# arduino_Uno_Rev3-02-TH.net
KiCad netlist of a schematic drawn in EAGLE
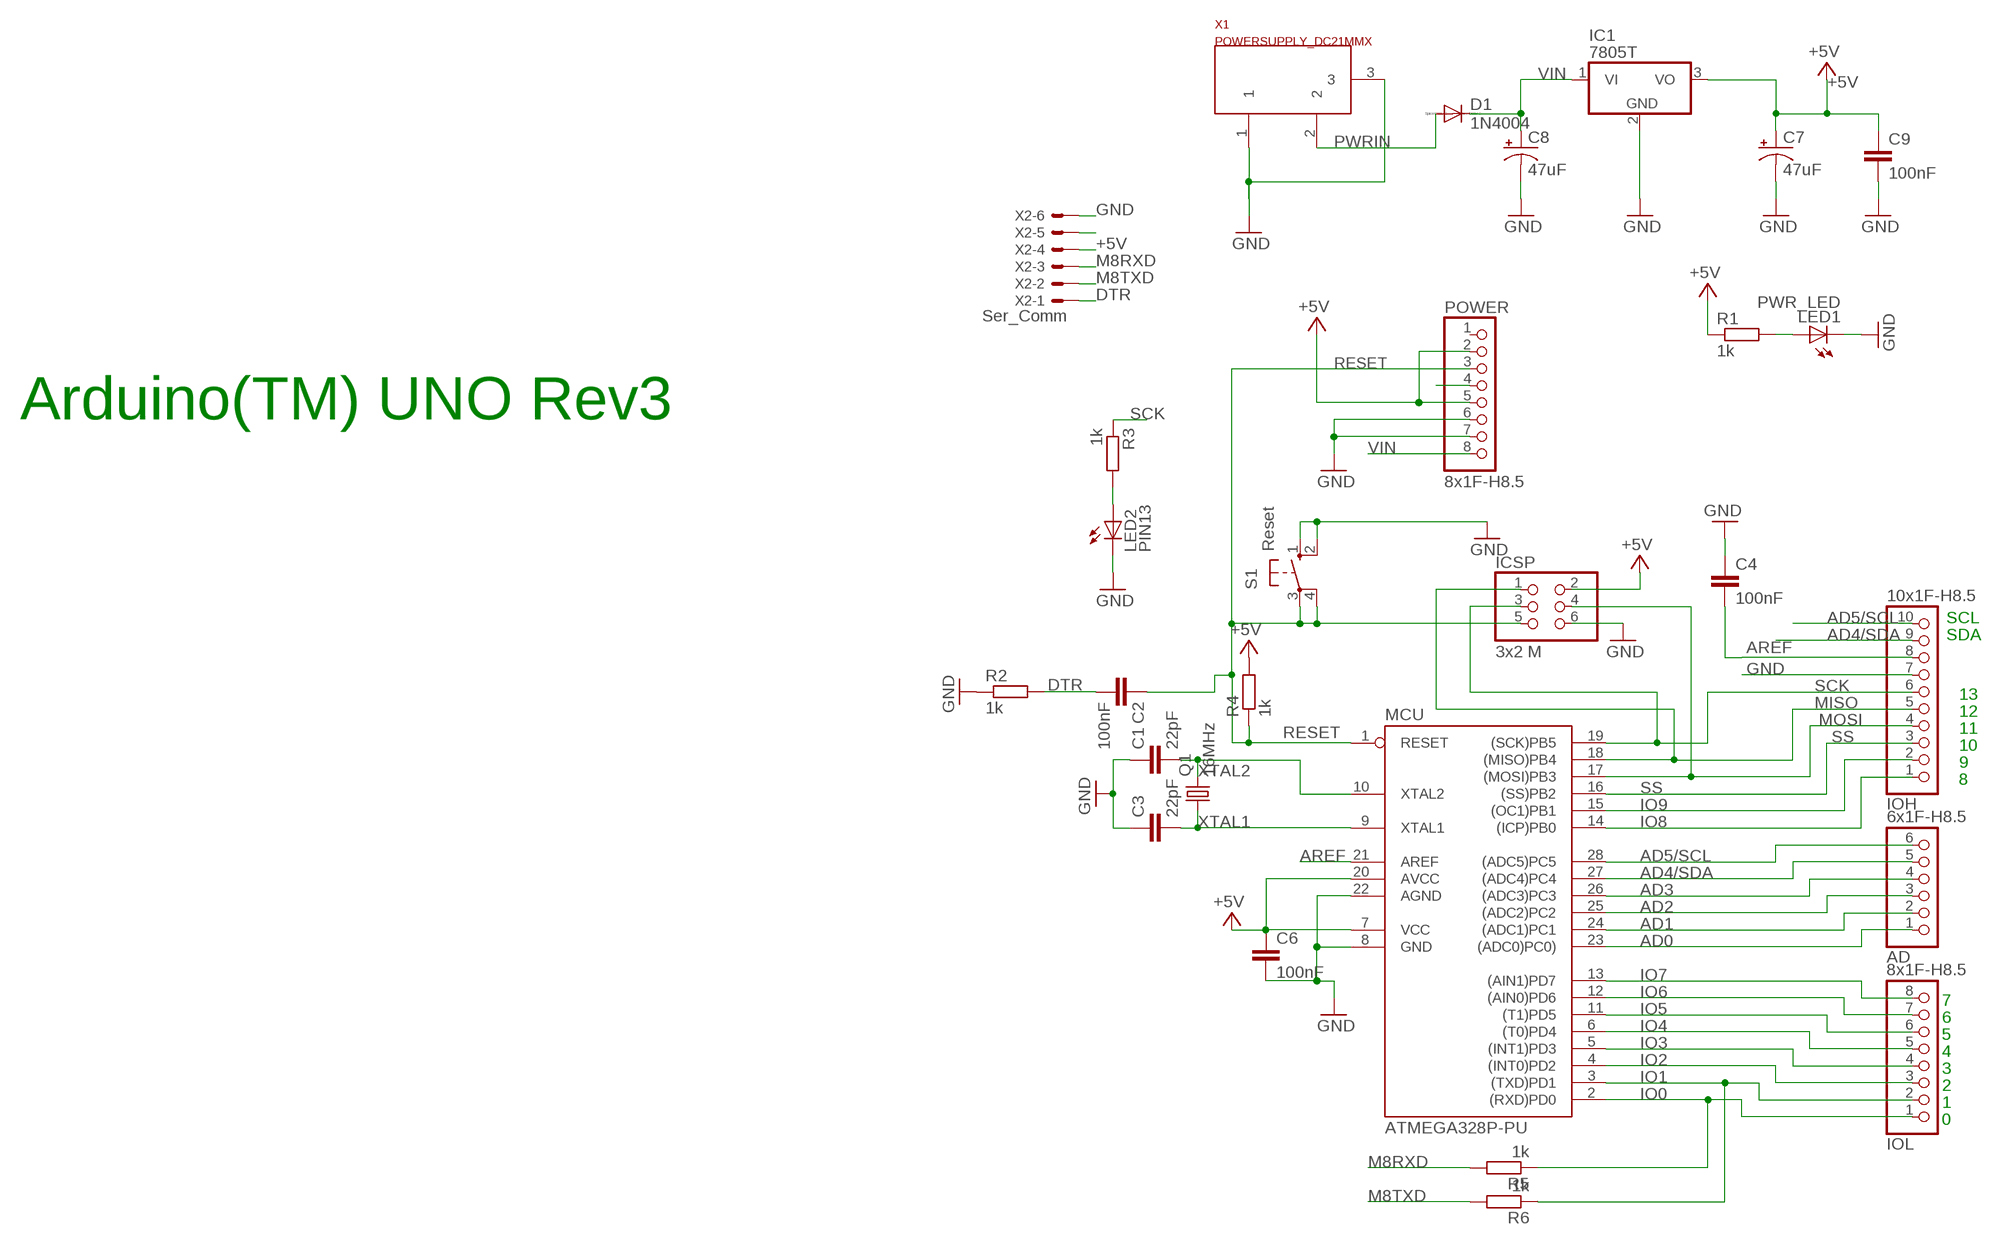
[diagram p0: schematic, sheet 1]

(export (version "E")
  (design (tool "Eeschema 10.0.6"))
  (components
    (comp (ref "AD")
      (value "6x1F-H8.5")
      (footprint "eagle-import:1X06")
      (libsource (lib "eagle-import") (part "PINHD-1X6"))
    )
    (comp (ref "C1")
      (value "22pF")
      (footprint "eagle-import:C2.5-2")
      (libsource (lib "eagle-import") (part "C2.5/2"))
    )
    (comp (ref "C2")
      (value "100nF")
      (footprint "eagle-import:C2.5-3")
      (libsource (lib "eagle-import") (part "C2,5-3"))
    )
    (comp (ref "C3")
      (value "22pF")
      (footprint "eagle-import:C2.5-2")
      (libsource (lib "eagle-import") (part "C2.5/2"))
    )
    (comp (ref "C4")
      (value "100nF")
      (footprint "eagle-import:C2.5-3")
      (libsource (lib "eagle-import") (part "C2,5-3"))
    )
    (comp (ref "C6")
      (value "100nF")
      (footprint "eagle-import:C2.5-3")
      (libsource (lib "eagle-import") (part "C2,5-3"))
    )
    (comp (ref "C7")
      (value "47uF")
      (footprint "eagle-import:E3,5-8")
      (libsource (lib "eagle-import") (part "CPOL-USE3.5-8"))
    )
    (comp (ref "C8")
      (value "47uF")
      (footprint "eagle-import:E3,5-8")
      (libsource (lib "eagle-import") (part "CPOL-USE3.5-8"))
    )
    (comp (ref "C9")
      (value "100nF")
      (footprint "eagle-import:C2.5-3")
      (libsource (lib "eagle-import") (part "C2,5-3"))
    )
    (comp (ref "D1")
      (value "1N4004")
      (footprint "eagle-import:DO41-10")
      (libsource (lib "eagle-import") (part "1N4004"))
    )
    (comp (ref "IC1")
      (value "7805T")
      (footprint "eagle-import:TO220H")
      (libsource (lib "eagle-import") (part "78T05"))
    )
    (comp (ref "ICSP")
      (value "3x2 M")
      (footprint "eagle-import:2X03")
      (libsource (lib "eagle-import") (part "PINHD-2X3"))
    )
    (comp (ref "IOH")
      (value "10x1F-H8.5")
      (footprint "eagle-import:1X10")
      (libsource (lib "eagle-import") (part "PINHD-1X10_ARD"))
    )
    (comp (ref "IOL")
      (value "8x1F-H8.5")
      (footprint "eagle-import:1X08")
      (libsource (lib "eagle-import") (part "PINHD-1X8"))
    )
    (comp (ref "LED1")
      (value "PWR_LED")
      (footprint "eagle-import:LED3MM")
      (libsource (lib "eagle-import") (part "LED3MM"))
    )
    (comp (ref "LED2")
      (value "PIN13")
      (footprint "eagle-import:LED5MM")
      (libsource (lib "eagle-import") (part "LED5MM"))
    )
    (comp (ref "MCU")
      (value "ATMEGA328P-PU")
      (footprint "eagle-import:DIL28-3")
      (libsource (lib "eagle-import") (part "ATMEGA328P-PU"))
    )
    (comp (ref "POWER")
      (value "8x1F-H8.5")
      (footprint "eagle-import:1X08")
      (libsource (lib "eagle-import") (part "PINHD-1X8"))
    )
    (comp (ref "Q1")
      (value "16MHz")
      (footprint "eagle-import:HC49_S")
      (libsource (lib "eagle-import") (part "CRYSTALHC49S"))
    )
    (comp (ref "R1")
      (value "1k")
      (footprint "eagle-import:0207_10")
      (libsource (lib "eagle-import") (part "R-EU_0207/10"))
    )
    (comp (ref "R2")
      (value "1k")
      (footprint "eagle-import:0207_10")
      (libsource (lib "eagle-import") (part "R-EU_0207/10"))
    )
    (comp (ref "R3")
      (value "1k")
      (footprint "eagle-import:0207_10")
      (libsource (lib "eagle-import") (part "R-EU_0207/10"))
    )
    (comp (ref "R4")
      (value "1k")
      (footprint "eagle-import:0207_10")
      (libsource (lib "eagle-import") (part "R-EU_0207/10"))
    )
    (comp (ref "R5")
      (value "1k")
      (footprint "eagle-import:0207_10")
      (libsource (lib "eagle-import") (part "R-EU_0207/10"))
    )
    (comp (ref "R6")
      (value "1k")
      (footprint "eagle-import:0207_10")
      (libsource (lib "eagle-import") (part "R-EU_0207/10"))
    )
    (comp (ref "S1")
      (value "Reset")
      (footprint "eagle-import:B3F-10XX")
      (fields (field (name "MPN") "B3F-1000"))
      (libsource (lib "eagle-import") (part "10-XX"))
    )
    (comp (ref "X1")
      (value "POWERSUPPLY_DC21MMX")
      (footprint "eagle-import:POWERSUPPLY_DC-21MM")
      (libsource (lib "eagle-import") (part "POWERSUPPLY_DC21MMX"))
    )
    (comp (ref "X2")
      (value "Ser_Comm")
      (footprint "eagle-import:22-23-2061")
      (fields (field (name "MF") "MOLEX") (field (name "MPN") "22-23-2061"))
      (libsource (lib "eagle-import") (part "22-23-2061"))
    )
  )
  (nets
    (net (code "1") (name "+5V") (class "Default")
      (node (ref "C6") (pin "1") (pinfunction "1_1") (pintype "passive"))
      (node (ref "C7") (pin "+") (pinfunction "+_+") (pintype "passive"))
      (node (ref "C9") (pin "1") (pinfunction "1_1") (pintype "passive"))
      (node (ref "IC1") (pin "3") (pinfunction "VO_3") (pintype "passive"))
      (node (ref "ICSP") (pin "2") (pinfunction "2_2") (pintype "passive"))
      (node (ref "MCU") (pin "20") (pinfunction "AVCC_20") (pintype "power_in"))
      (node (ref "MCU") (pin "7") (pinfunction "VCC_7") (pintype "power_in"))
      (node (ref "POWER") (pin "2") (pinfunction "2_2") (pintype "passive"))
      (node (ref "POWER") (pin "5") (pinfunction "5_5") (pintype "passive"))
      (node (ref "R1") (pin "1") (pinfunction "1_1") (pintype "passive"))
      (node (ref "R4") (pin "2") (pinfunction "2_2") (pintype "passive"))
      (node (ref "X2") (pin "4") (pinfunction "S_4") (pintype "passive"))
    )
    (net (code "2") (name "/AD0") (class "Default")
      (node (ref "AD") (pin "1") (pinfunction "1_1") (pintype "passive"))
      (node (ref "MCU") (pin "23") (pinfunction "(ADC0)PC0)_23") (pintype "bidirectional"))
    )
    (net (code "3") (name "/AD1") (class "Default")
      (node (ref "AD") (pin "2") (pinfunction "2_2") (pintype "passive"))
      (node (ref "MCU") (pin "24") (pinfunction "(ADC1)PC1_24") (pintype "bidirectional"))
    )
    (net (code "4") (name "/AD2") (class "Default")
      (node (ref "AD") (pin "3") (pinfunction "3_3") (pintype "passive"))
      (node (ref "MCU") (pin "25") (pinfunction "(ADC2)PC2_25") (pintype "bidirectional"))
    )
    (net (code "5") (name "/AD3") (class "Default")
      (node (ref "AD") (pin "4") (pinfunction "4_4") (pintype "passive"))
      (node (ref "MCU") (pin "26") (pinfunction "(ADC3)PC3_26") (pintype "bidirectional"))
    )
    (net (code "6") (name "/AD4{slash}SDA") (class "Default")
      (node (ref "AD") (pin "5") (pinfunction "5_5") (pintype "passive"))
      (node (ref "IOH") (pin "9") (pinfunction "9_9") (pintype "passive"))
      (node (ref "MCU") (pin "27") (pinfunction "(ADC4)PC4_27") (pintype "bidirectional"))
    )
    (net (code "7") (name "/AD5{slash}SCL") (class "Default")
      (node (ref "AD") (pin "6") (pinfunction "6_6") (pintype "passive"))
      (node (ref "IOH") (pin "10") (pinfunction "10_10") (pintype "passive"))
      (node (ref "MCU") (pin "28") (pinfunction "(ADC5)PC5_28") (pintype "bidirectional"))
    )
    (net (code "8") (name "/AREF") (class "Default")
      (node (ref "C4") (pin "2") (pinfunction "2_2") (pintype "passive"))
      (node (ref "IOH") (pin "8") (pinfunction "8_8") (pintype "passive"))
      (node (ref "MCU") (pin "21") (pinfunction "AREF_21") (pintype "passive"))
    )
    (net (code "9") (name "/DTR") (class "Default")
      (node (ref "C2") (pin "2") (pinfunction "2_2") (pintype "passive"))
      (node (ref "R2") (pin "2") (pinfunction "2_2") (pintype "passive"))
      (node (ref "X2") (pin "1") (pinfunction "S_1") (pintype "passive"))
    )
    (net (code "10") (name "/IO0") (class "Default")
      (node (ref "IOL") (pin "1") (pinfunction "1_1") (pintype "passive"))
      (node (ref "MCU") (pin "2") (pinfunction "(RXD)PD0_2") (pintype "bidirectional"))
      (node (ref "R5") (pin "1") (pinfunction "1_1") (pintype "passive"))
    )
    (net (code "11") (name "/IO1") (class "Default")
      (node (ref "IOL") (pin "2") (pinfunction "2_2") (pintype "passive"))
      (node (ref "MCU") (pin "3") (pinfunction "(TXD)PD1_3") (pintype "bidirectional"))
      (node (ref "R6") (pin "1") (pinfunction "1_1") (pintype "passive"))
    )
    (net (code "12") (name "/IO2") (class "Default")
      (node (ref "IOL") (pin "3") (pinfunction "3_3") (pintype "passive"))
      (node (ref "MCU") (pin "4") (pinfunction "(INT0)PD2_4") (pintype "bidirectional"))
    )
    (net (code "13") (name "/IO3") (class "Default")
      (node (ref "IOL") (pin "4") (pinfunction "4_4") (pintype "passive"))
      (node (ref "MCU") (pin "5") (pinfunction "(INT1)PD3_5") (pintype "bidirectional"))
    )
    (net (code "14") (name "/IO4") (class "Default")
      (node (ref "IOL") (pin "5") (pinfunction "5_5") (pintype "passive"))
      (node (ref "MCU") (pin "6") (pinfunction "(T0)PD4_6") (pintype "bidirectional"))
    )
    (net (code "15") (name "/IO5") (class "Default")
      (node (ref "IOL") (pin "6") (pinfunction "6_6") (pintype "passive"))
      (node (ref "MCU") (pin "11") (pinfunction "(T1)PD5_11") (pintype "bidirectional"))
    )
    (net (code "16") (name "/IO6") (class "Default")
      (node (ref "IOL") (pin "7") (pinfunction "7_7") (pintype "passive"))
      (node (ref "MCU") (pin "12") (pinfunction "(AIN0)PD6_12") (pintype "bidirectional"))
    )
    (net (code "17") (name "/IO7") (class "Default")
      (node (ref "IOL") (pin "8") (pinfunction "8_8") (pintype "passive"))
      (node (ref "MCU") (pin "13") (pinfunction "(AIN1)PD7_13") (pintype "bidirectional"))
    )
    (net (code "18") (name "/IO8") (class "Default")
      (node (ref "IOH") (pin "1") (pinfunction "1_1") (pintype "passive"))
      (node (ref "MCU") (pin "14") (pinfunction "(ICP)PB0_14") (pintype "bidirectional"))
    )
    (net (code "19") (name "/IO9") (class "Default")
      (node (ref "IOH") (pin "2") (pinfunction "2_2") (pintype "passive"))
      (node (ref "MCU") (pin "15") (pinfunction "(OC1)PB1_15") (pintype "bidirectional"))
    )
    (net (code "20") (name "/M8RXD") (class "Default")
      (node (ref "R5") (pin "2") (pinfunction "2_2") (pintype "passive"))
      (node (ref "X2") (pin "3") (pinfunction "S_3") (pintype "passive"))
    )
    (net (code "21") (name "/M8TXD") (class "Default")
      (node (ref "R6") (pin "2") (pinfunction "2_2") (pintype "passive"))
      (node (ref "X2") (pin "2") (pinfunction "S_2") (pintype "passive"))
    )
    (net (code "22") (name "/MISO") (class "Default")
      (node (ref "ICSP") (pin "1") (pinfunction "1_1") (pintype "passive"))
      (node (ref "IOH") (pin "5") (pinfunction "5_5") (pintype "passive"))
      (node (ref "MCU") (pin "18") (pinfunction "(MISO)PB4_18") (pintype "bidirectional"))
    )
    (net (code "23") (name "/MOSI") (class "Default")
      (node (ref "ICSP") (pin "4") (pinfunction "4_4") (pintype "passive"))
      (node (ref "IOH") (pin "4") (pinfunction "4_4") (pintype "passive"))
      (node (ref "MCU") (pin "17") (pinfunction "(MOSI)PB3_17") (pintype "bidirectional"))
    )
    (net (code "24") (name "/PWRIN") (class "Default")
      (node (ref "D1") (pin "A") (pinfunction "A_A") (pintype "passive"))
      (node (ref "X1") (pin "2") (pinfunction "2_2") (pintype "power_in"))
    )
    (net (code "25") (name "/RESET") (class "Default")
      (node (ref "C2") (pin "1") (pinfunction "1_1") (pintype "passive"))
      (node (ref "ICSP") (pin "5") (pinfunction "5_5") (pintype "passive"))
      (node (ref "MCU") (pin "1") (pinfunction "RESET_1") (pintype "input"))
      (node (ref "POWER") (pin "3") (pinfunction "3_3") (pintype "passive"))
      (node (ref "R4") (pin "1") (pinfunction "1_1") (pintype "passive"))
      (node (ref "S1") (pin "3") (pinfunction "P_3") (pintype "passive"))
      (node (ref "S1") (pin "4") (pinfunction "P1_4") (pintype "passive"))
    )
    (net (code "26") (name "/SCK") (class "Default")
      (node (ref "ICSP") (pin "3") (pinfunction "3_3") (pintype "passive"))
      (node (ref "IOH") (pin "6") (pinfunction "6_6") (pintype "passive"))
      (node (ref "MCU") (pin "19") (pinfunction "(SCK)PB5_19") (pintype "bidirectional"))
      (node (ref "R3") (pin "1") (pinfunction "1_1") (pintype "passive"))
    )
    (net (code "27") (name "/SS") (class "Default")
      (node (ref "IOH") (pin "3") (pinfunction "3_3") (pintype "passive"))
      (node (ref "MCU") (pin "16") (pinfunction "(SS)PB2_16") (pintype "bidirectional"))
    )
    (net (code "28") (name "/VIN") (class "Default")
      (node (ref "C8") (pin "+") (pinfunction "+_+") (pintype "passive"))
      (node (ref "D1") (pin "C") (pinfunction "C_C") (pintype "passive"))
      (node (ref "IC1") (pin "1") (pinfunction "VI_1") (pintype "input"))
      (node (ref "POWER") (pin "8") (pinfunction "8_8") (pintype "passive"))
    )
    (net (code "29") (name "/XTAL1") (class "Default")
      (node (ref "C3") (pin "2") (pinfunction "2_2") (pintype "passive"))
      (node (ref "MCU") (pin "9") (pinfunction "XTAL1_9") (pintype "bidirectional"))
      (node (ref "Q1") (pin "1") (pinfunction "1_1") (pintype "passive"))
    )
    (net (code "30") (name "/XTAL2") (class "Default")
      (node (ref "C1") (pin "2") (pinfunction "2_2") (pintype "passive"))
      (node (ref "MCU") (pin "10") (pinfunction "XTAL2_10") (pintype "bidirectional"))
      (node (ref "Q1") (pin "2") (pinfunction "2_2") (pintype "passive"))
    )
    (net (code "31") (name "GND") (class "Default")
      (node (ref "C1") (pin "1") (pinfunction "1_1") (pintype "passive"))
      (node (ref "C3") (pin "1") (pinfunction "1_1") (pintype "passive"))
      (node (ref "C4") (pin "1") (pinfunction "1_1") (pintype "passive"))
      (node (ref "C6") (pin "2") (pinfunction "2_2") (pintype "passive"))
      (node (ref "C7") (pin "-") (pinfunction "-_-") (pintype "passive"))
      (node (ref "C8") (pin "-") (pinfunction "-_-") (pintype "passive"))
      (node (ref "C9") (pin "2") (pinfunction "2_2") (pintype "passive"))
      (node (ref "IC1") (pin "2") (pinfunction "GND_2") (pintype "passive"))
      (node (ref "ICSP") (pin "6") (pinfunction "6_6") (pintype "passive"))
      (node (ref "IOH") (pin "7") (pinfunction "7_7") (pintype "passive"))
      (node (ref "LED1") (pin "K") (pinfunction "C_K") (pintype "passive"))
      (node (ref "LED2") (pin "K") (pinfunction "C_K") (pintype "passive"))
      (node (ref "MCU") (pin "22") (pinfunction "AGND_22") (pintype "power_in"))
      (node (ref "MCU") (pin "8") (pinfunction "GND_8") (pintype "power_in"))
      (node (ref "POWER") (pin "6") (pinfunction "6_6") (pintype "passive"))
      (node (ref "POWER") (pin "7") (pinfunction "7_7") (pintype "passive"))
      (node (ref "R2") (pin "1") (pinfunction "1_1") (pintype "passive"))
      (node (ref "S1") (pin "1") (pinfunction "S_1") (pintype "passive"))
      (node (ref "S1") (pin "2") (pinfunction "S1_2") (pintype "passive"))
      (node (ref "X1") (pin "1") (pinfunction "1_1") (pintype "power_in"))
      (node (ref "X1") (pin "3") (pinfunction "3_3") (pintype "power_in"))
      (node (ref "X2") (pin "6") (pinfunction "S_6") (pintype "passive"))
    )
    (net (code "32") (name "Net-(LED1-PadA)") (class "Default")
      (node (ref "LED1") (pin "A") (pinfunction "A_A") (pintype "passive"))
      (node (ref "R1") (pin "2") (pinfunction "2_2") (pintype "passive"))
    )
    (net (code "33") (name "Net-(LED2-PadA)") (class "Default")
      (node (ref "LED2") (pin "A") (pinfunction "A_A") (pintype "passive"))
      (node (ref "R3") (pin "2") (pinfunction "2_2") (pintype "passive"))
    )
    (net (code "34") (name "unconnected-(POWER-Pad1)") (class "Default")
      (node (ref "POWER") (pin "1") (pinfunction "1_1") (pintype "passive"))
    )
    (net (code "35") (name "unconnected-(POWER-Pad4)") (class "Default")
      (node (ref "POWER") (pin "4") (pinfunction "4_4") (pintype "passive"))
    )
    (net (code "36") (name "unconnected-(X2E-S-Pad5)") (class "Default")
      (node (ref "X2") (pin "5") (pinfunction "S_5") (pintype "passive"))
    )
  )
)
